# can-udp-bridge.net
KiCad netlist of a schematic drawn in EAGLE
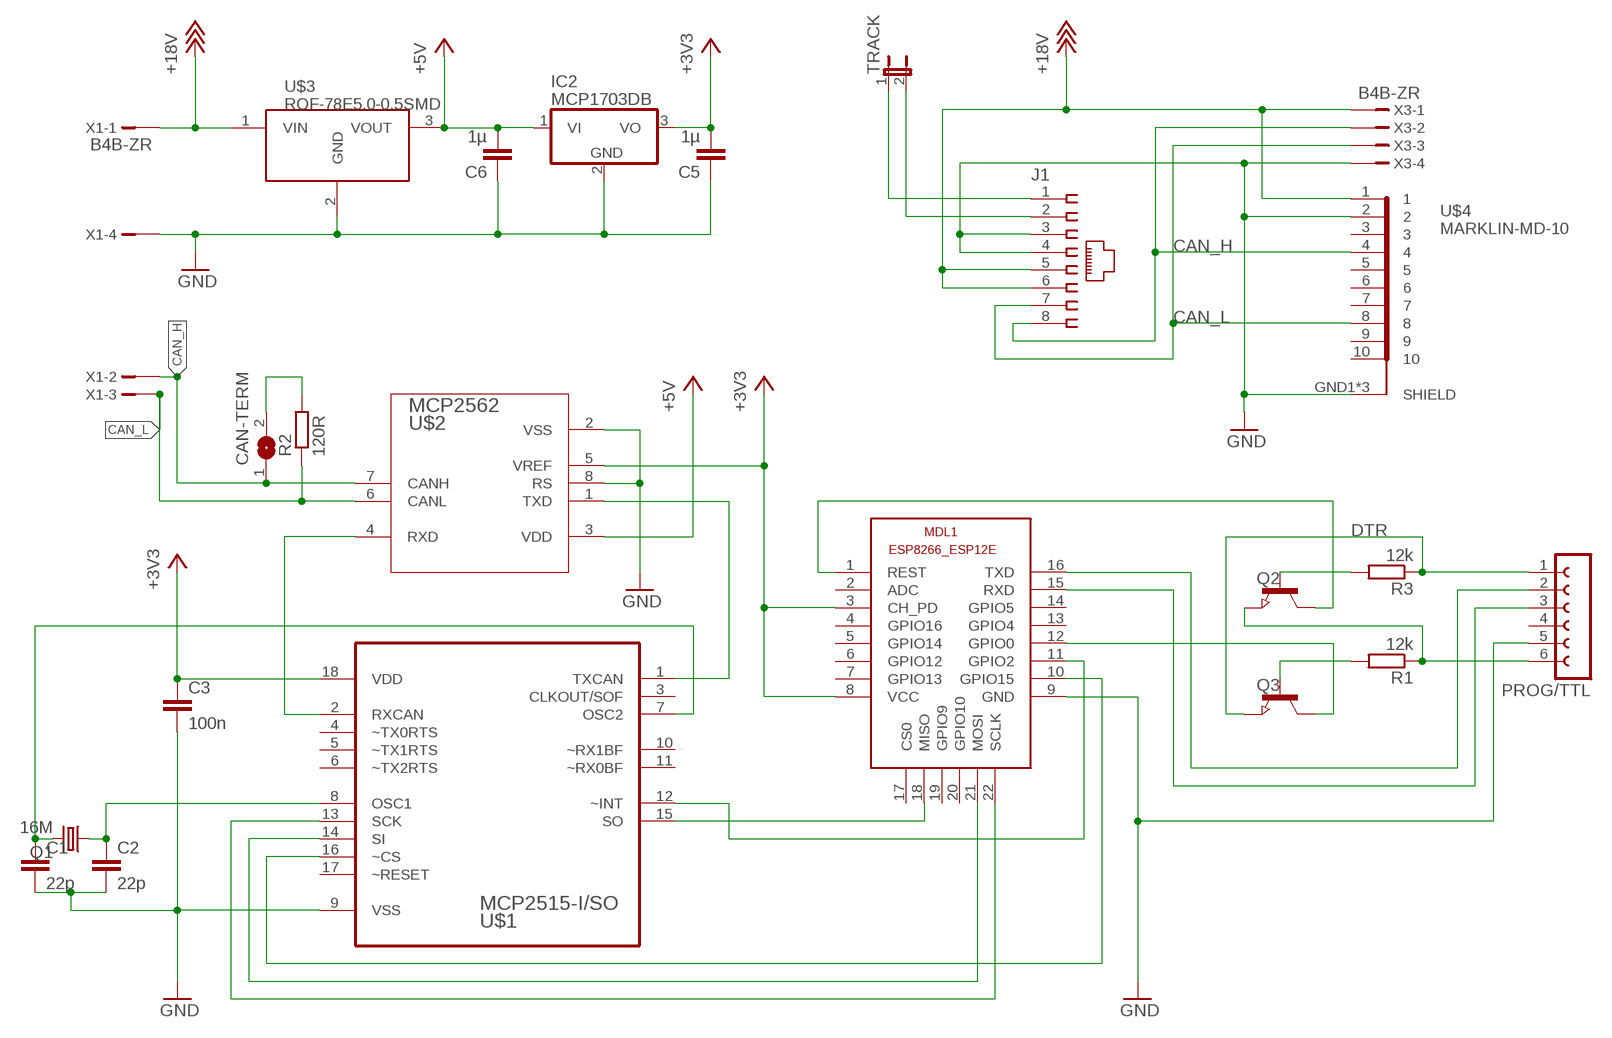
[diagram p0: schematic, sheet 1]

(export (version "E")
  (design (tool "Eeschema 10.0.6"))
  (components
    (comp (ref "C1")
      (value "22p")
      (footprint "eagle-import:C0805")
      (libsource (lib "eagle-import") (part "C-EUC0805"))
    )
    (comp (ref "C2")
      (value "22p")
      (footprint "eagle-import:C0805")
      (libsource (lib "eagle-import") (part "C-EUC0805"))
    )
    (comp (ref "C3")
      (value "100n")
      (footprint "eagle-import:C0805")
      (libsource (lib "eagle-import") (part "C-EUC0805"))
    )
    (comp (ref "C5")
      (value "1µ")
      (footprint "eagle-import:C0805")
      (libsource (lib "eagle-import") (part "C-EUC0805"))
    )
    (comp (ref "C6")
      (value "1µ")
      (footprint "eagle-import:C0805")
      (libsource (lib "eagle-import") (part "C-EUC0805"))
    )
    (comp (ref "CAN-TERM")
      (value "SJ")
      (footprint "eagle-import:SJ")
      (libsource (lib "eagle-import") (part "SJ"))
    )
    (comp (ref "IC2")
      (value "MCP1703DB")
      (footprint "eagle-import:SOT223")
      (libsource (lib "eagle-import") (part "MCP1703DB"))
    )
    (comp (ref "J1")
      (value "215877-7")
      (footprint "eagle-import:215877-7")
      (libsource (lib "eagle-import") (part "215877-7"))
    )
    (comp (ref "MDL1")
      (value "ESP8266-12EESP8266-ESP12E")
      (footprint "eagle-import:ESP8266-ESP12E")
      (libsource (lib "eagle-import") (part "ESP8266-12EESP8266-ESP12E"))
    )
    (comp (ref "PROG/TTL")
      (value "FE06W")
      (footprint "eagle-import:FE06W")
      (libsource (lib "eagle-import") (part "FE06W"))
    )
    (comp (ref "Q1")
      (value "16M")
      (footprint "eagle-import:CTS406")
      (libsource (lib "eagle-import") (part "CRYSTALCTS406"))
    )
    (comp (ref "Q2")
      (value "NPN-TRANSISTOR_SOT23")
      (footprint "eagle-import:SOT23")
      (libsource (lib "eagle-import") (part "NPN-TRANSISTOR_SOT23"))
    )
    (comp (ref "Q3")
      (value "NPN-TRANSISTOR_SOT23")
      (footprint "eagle-import:SOT23")
      (libsource (lib "eagle-import") (part "NPN-TRANSISTOR_SOT23"))
    )
    (comp (ref "R1")
      (value "12k")
      (footprint "eagle-import:R0805")
      (libsource (lib "eagle-import") (part "R-EU_R0805"))
    )
    (comp (ref "R2")
      (value "120R")
      (footprint "eagle-import:R0805")
      (libsource (lib "eagle-import") (part "R-EU_R0805"))
    )
    (comp (ref "R3")
      (value "12k")
      (footprint "eagle-import:R0805")
      (libsource (lib "eagle-import") (part "R-EU_R0805"))
    )
    (comp (ref "TRACK")
      (value "JP1E")
      (footprint "eagle-import:JP1")
      (libsource (lib "eagle-import") (part "JP1E"))
    )
    (comp (ref "U$1")
      (value "MCP2515-I/SO")
      (footprint "eagle-import:SOIC127P1034X264-18N")
      (libsource (lib "eagle-import") (part "MCP2515-I/SO"))
    )
    (comp (ref "U$2")
      (value "MCP2562")
      (footprint "eagle-import:SOIC127P600X175-8N")
      (fields (field (name "MPN") "MCP2551-E/SN"))
      (libsource (lib "eagle-import") (part "MCP2551-E/SN"))
    )
    (comp (ref "U$3")
      (value "ROF-78E5.0-0.5SMD")
      (footprint "eagle-import:ROF-78EXX-0.5SMD")
      (libsource (lib "eagle-import") (part "ROF-78E5.0-0.5SMD"))
    )
    (comp (ref "U$4")
      (value "MARKLIN-MD-10")
      (footprint "eagle-import:MARKLIN-MD-10-PRINT")
      (libsource (lib "eagle-import") (part "MARKLIN-MD-10"))
    )
    (comp (ref "X1")
      (value "B4B-ZR")
      (footprint "eagle-import:B4B-ZR")
      (fields (field (name "MF") "FARNELL") (field (name "MPN") "B4B-ZR(LF)(SN)"))
      (libsource (lib "eagle-import") (part "?4B-ZRB"))
    )
    (comp (ref "X3")
      (value "B4B-ZR")
      (footprint "eagle-import:B4B-ZR")
      (fields (field (name "MF") "FARNELL") (field (name "MPN") "B4B-ZR(LF)(SN)"))
      (libsource (lib "eagle-import") (part "?4B-ZRB"))
    )
  )
  (nets
    (net (code "1") (name "+3V3") (class "Default")
      (node (ref "C3") (pin "1") (pinfunction "1_1") (pintype "passive"))
      (node (ref "C5") (pin "2") (pinfunction "2_2") (pintype "passive"))
      (node (ref "IC2") (pin "3") (pinfunction "VO_3") (pintype "passive"))
      (node (ref "MDL1") (pin "3") (pinfunction "CH_PD_3") (pintype "bidirectional"))
      (node (ref "MDL1") (pin "8") (pinfunction "VCC_8") (pintype "bidirectional"))
      (node (ref "U$1") (pin "18") (pinfunction "VDD_18") (pintype "power_in"))
      (node (ref "U$2") (pin "5") (pinfunction "VREF_5") (pintype "input"))
    )
    (net (code "2") (name "+5V") (class "Default")
      (node (ref "C6") (pin "2") (pinfunction "2_2") (pintype "passive"))
      (node (ref "IC2") (pin "1") (pinfunction "VI_1") (pintype "input"))
      (node (ref "U$2") (pin "3") (pinfunction "VDD_3") (pintype "power_in"))
      (node (ref "U$3") (pin "3") (pinfunction "VOUT_3") (pintype "bidirectional"))
    )
    (net (code "3") (name "+18V") (class "Default")
      (node (ref "J1") (pin "5") (pinfunction "5_5") (pintype "passive"))
      (node (ref "J1") (pin "6") (pinfunction "6_6") (pintype "passive"))
      (node (ref "U$3") (pin "1") (pinfunction "VIN_1") (pintype "bidirectional"))
      (node (ref "U$4") (pin "1") (pinfunction "1_1") (pintype "bidirectional"))
      (node (ref "X1") (pin "1") (pinfunction "1_1") (pintype "passive"))
      (node (ref "X3") (pin "1") (pinfunction "1_1") (pintype "passive"))
    )
    (net (code "4") (name "/DTR") (class "Default")
      (node (ref "PROG/TTL") (pin "1") (pinfunction "1_1") (pintype "passive"))
      (node (ref "Q3") (pin "2") (pinfunction "E_2") (pintype "passive"))
      (node (ref "R3") (pin "1") (pinfunction "1_1") (pintype "passive"))
    )
    (net (code "5") (name "CAN_H") (class "Default")
      (node (ref "CAN-TERM") (pin "1") (pinfunction "1_1") (pintype "passive"))
      (node (ref "J1") (pin "8") (pinfunction "8_8") (pintype "passive"))
      (node (ref "U$2") (pin "7") (pinfunction "CANH_7") (pintype "output"))
      (node (ref "U$4") (pin "4") (pinfunction "4_4") (pintype "bidirectional"))
      (node (ref "X1") (pin "2") (pinfunction "1_2") (pintype "passive"))
      (node (ref "X3") (pin "2") (pinfunction "1_2") (pintype "passive"))
    )
    (net (code "6") (name "CAN_L") (class "Default")
      (node (ref "J1") (pin "7") (pinfunction "7_7") (pintype "passive"))
      (node (ref "R2") (pin "1") (pinfunction "1_1") (pintype "passive"))
      (node (ref "U$2") (pin "6") (pinfunction "CANL_6") (pintype "output"))
      (node (ref "U$4") (pin "8") (pinfunction "8_8") (pintype "bidirectional"))
      (node (ref "X1") (pin "3") (pinfunction "1_3") (pintype "passive"))
      (node (ref "X3") (pin "3") (pinfunction "1_3") (pintype "passive"))
    )
    (net (code "7") (name "GND") (class "Default")
      (node (ref "C1") (pin "2") (pinfunction "2_2") (pintype "passive"))
      (node (ref "C2") (pin "2") (pinfunction "2_2") (pintype "passive"))
      (node (ref "C3") (pin "2") (pinfunction "2_2") (pintype "passive"))
      (node (ref "C5") (pin "1") (pinfunction "1_1") (pintype "passive"))
      (node (ref "C6") (pin "1") (pinfunction "1_1") (pintype "passive"))
      (node (ref "IC2") (pin "2") (pinfunction "GND_2") (pintype "passive"))
      (node (ref "J1") (pin "3") (pinfunction "3_3") (pintype "passive"))
      (node (ref "J1") (pin "4") (pinfunction "4_4") (pintype "passive"))
      (node (ref "MDL1") (pin "9") (pinfunction "GND_9") (pintype "bidirectional"))
      (node (ref "PROG/TTL") (pin "5") (pinfunction "5_5") (pintype "passive"))
      (node (ref "U$1") (pin "9") (pinfunction "VSS_9") (pintype "power_in"))
      (node (ref "U$2") (pin "2") (pinfunction "VSS_2") (pintype "power_in"))
      (node (ref "U$2") (pin "8") (pinfunction "RS_8") (pintype "input"))
      (node (ref "U$3") (pin "2") (pinfunction "GND_2") (pintype "bidirectional"))
      (node (ref "U$4") (pin "2") (pinfunction "2_2") (pintype "bidirectional"))
      (node (ref "U$4") (pin "GND1") (pinfunction "SHIELD_GND1") (pintype "bidirectional"))
      (node (ref "U$4") (pin "GND2") (pinfunction "SHIELD_GND2") (pintype "bidirectional"))
      (node (ref "U$4") (pin "GND3") (pinfunction "SHIELD_GND3") (pintype "bidirectional"))
      (node (ref "X1") (pin "4") (pinfunction "1_4") (pintype "passive"))
      (node (ref "X3") (pin "4") (pinfunction "1_4") (pintype "passive"))
    )
    (net (code "8") (name "Net-(CAN-TERM-Pad2)") (class "Default")
      (node (ref "CAN-TERM") (pin "2") (pinfunction "2_2") (pintype "passive"))
      (node (ref "R2") (pin "2") (pinfunction "2_2") (pintype "passive"))
    )
    (net (code "9") (name "Net-(J1-Pad1)") (class "Default")
      (node (ref "J1") (pin "1") (pinfunction "1_1") (pintype "passive"))
      (node (ref "TRACK") (pin "1") (pinfunction "1_1") (pintype "passive"))
    )
    (net (code "10") (name "Net-(J1-Pad2)") (class "Default")
      (node (ref "J1") (pin "2") (pinfunction "2_2") (pintype "passive"))
      (node (ref "TRACK") (pin "2") (pinfunction "2_2") (pintype "passive"))
    )
    (net (code "11") (name "Net-(MDL1-GPIO0)") (class "Default")
      (node (ref "MDL1") (pin "12") (pinfunction "GPIO0_12") (pintype "bidirectional"))
      (node (ref "Q3") (pin "3") (pinfunction "C_3") (pintype "passive"))
    )
    (net (code "12") (name "Net-(MDL1-GPIO2)") (class "Default")
      (node (ref "MDL1") (pin "11") (pinfunction "GPIO2_11") (pintype "bidirectional"))
      (node (ref "U$1") (pin "12") (pinfunction "~{INT}_12") (pintype "output"))
    )
    (net (code "13") (name "Net-(MDL1-GPIO15)") (class "Default")
      (node (ref "MDL1") (pin "10") (pinfunction "GPIO15_10") (pintype "bidirectional"))
      (node (ref "U$1") (pin "16") (pinfunction "~{CS}_16") (pintype "input"))
    )
    (net (code "14") (name "Net-(MDL1-MISO)") (class "Default")
      (node (ref "MDL1") (pin "18") (pinfunction "MISO_18") (pintype "bidirectional"))
      (node (ref "U$1") (pin "15") (pinfunction "SO_15") (pintype "output"))
    )
    (net (code "15") (name "Net-(MDL1-MOSI)") (class "Default")
      (node (ref "MDL1") (pin "21") (pinfunction "MOSI_21") (pintype "bidirectional"))
      (node (ref "U$1") (pin "14") (pinfunction "SI_14") (pintype "input"))
    )
    (net (code "16") (name "Net-(MDL1-REST)") (class "Default")
      (node (ref "MDL1") (pin "1") (pinfunction "REST_1") (pintype "bidirectional"))
      (node (ref "Q2") (pin "3") (pinfunction "C_3") (pintype "passive"))
    )
    (net (code "17") (name "Net-(MDL1-RXD)") (class "Default")
      (node (ref "MDL1") (pin "15") (pinfunction "RXD_15") (pintype "bidirectional"))
      (node (ref "PROG/TTL") (pin "3") (pinfunction "3_3") (pintype "passive"))
    )
    (net (code "18") (name "Net-(MDL1-SCLK)") (class "Default")
      (node (ref "MDL1") (pin "22") (pinfunction "SCLK_22") (pintype "bidirectional"))
      (node (ref "U$1") (pin "13") (pinfunction "SCK_13") (pintype "input"))
    )
    (net (code "19") (name "Net-(MDL1-TXD)") (class "Default")
      (node (ref "MDL1") (pin "16") (pinfunction "TXD_16") (pintype "bidirectional"))
      (node (ref "PROG/TTL") (pin "2") (pinfunction "2_2") (pintype "passive"))
    )
    (net (code "20") (name "Net-(Q1-2)") (class "Default")
      (node (ref "C1") (pin "1") (pinfunction "1_1") (pintype "passive"))
      (node (ref "Q1") (pin "3") (pinfunction "2_3") (pintype "passive"))
      (node (ref "U$1") (pin "7") (pinfunction "OSC2_7") (pintype "output"))
    )
    (net (code "21") (name "Net-(Q2-B)") (class "Default")
      (node (ref "Q2") (pin "1") (pinfunction "B_1") (pintype "passive"))
      (node (ref "R3") (pin "2") (pinfunction "2_2") (pintype "passive"))
    )
    (net (code "22") (name "Net-(Q2-E)") (class "Default")
      (node (ref "PROG/TTL") (pin "6") (pinfunction "6_6") (pintype "passive"))
      (node (ref "Q2") (pin "2") (pinfunction "E_2") (pintype "passive"))
      (node (ref "R1") (pin "1") (pinfunction "1_1") (pintype "passive"))
    )
    (net (code "23") (name "Net-(Q3-B)") (class "Default")
      (node (ref "Q3") (pin "1") (pinfunction "B_1") (pintype "passive"))
      (node (ref "R1") (pin "2") (pinfunction "2_2") (pintype "passive"))
    )
    (net (code "24") (name "Net-(U$1-OSC1)") (class "Default")
      (node (ref "C2") (pin "1") (pinfunction "1_1") (pintype "passive"))
      (node (ref "Q1") (pin "1") (pinfunction "1_1") (pintype "passive"))
      (node (ref "U$1") (pin "8") (pinfunction "OSC1_8") (pintype "input"))
    )
    (net (code "25") (name "Net-(U$1-RXCAN)") (class "Default")
      (node (ref "U$1") (pin "2") (pinfunction "RXCAN_2") (pintype "input"))
      (node (ref "U$2") (pin "4") (pinfunction "RXD_4") (pintype "output"))
    )
    (net (code "26") (name "Net-(U$1-TXCAN)") (class "Default")
      (node (ref "U$1") (pin "1") (pinfunction "TXCAN_1") (pintype "output"))
      (node (ref "U$2") (pin "1") (pinfunction "TXD_1") (pintype "input"))
    )
    (net (code "27") (name "unconnected-(MDL1-ADC-Pad2)") (class "Default")
      (node (ref "MDL1") (pin "2") (pinfunction "ADC_2") (pintype "bidirectional"))
    )
    (net (code "28") (name "unconnected-(MDL1-CS0-Pad17)") (class "Default")
      (node (ref "MDL1") (pin "17") (pinfunction "CS0_17") (pintype "bidirectional"))
    )
    (net (code "29") (name "unconnected-(MDL1-GPIO4-Pad13)") (class "Default")
      (node (ref "MDL1") (pin "13") (pinfunction "GPIO4_13") (pintype "bidirectional"))
    )
    (net (code "30") (name "unconnected-(MDL1-GPIO5-Pad14)") (class "Default")
      (node (ref "MDL1") (pin "14") (pinfunction "GPIO5_14") (pintype "bidirectional"))
    )
    (net (code "31") (name "unconnected-(MDL1-GPIO9-Pad19)") (class "Default")
      (node (ref "MDL1") (pin "19") (pinfunction "GPIO9_19") (pintype "bidirectional"))
    )
    (net (code "32") (name "unconnected-(MDL1-GPIO10-Pad20)") (class "Default")
      (node (ref "MDL1") (pin "20") (pinfunction "GPIO10_20") (pintype "bidirectional"))
    )
    (net (code "33") (name "unconnected-(MDL1-GPIO12-Pad6)") (class "Default")
      (node (ref "MDL1") (pin "6") (pinfunction "GPIO12_6") (pintype "bidirectional"))
    )
    (net (code "34") (name "unconnected-(MDL1-GPIO13-Pad7)") (class "Default")
      (node (ref "MDL1") (pin "7") (pinfunction "GPIO13_7") (pintype "bidirectional"))
    )
    (net (code "35") (name "unconnected-(MDL1-GPIO14-Pad5)") (class "Default")
      (node (ref "MDL1") (pin "5") (pinfunction "GPIO14_5") (pintype "bidirectional"))
    )
    (net (code "36") (name "unconnected-(MDL1-GPIO16-Pad4)") (class "Default")
      (node (ref "MDL1") (pin "4") (pinfunction "GPIO16_4") (pintype "bidirectional"))
    )
    (net (code "37") (name "unconnected-(PROG/TTL-Pad4)") (class "Default")
      (node (ref "PROG/TTL") (pin "4") (pinfunction "4_4") (pintype "passive"))
    )
    (net (code "38") (name "unconnected-(U$1-CLKOUT{slash}SOF-Pad3)") (class "Default")
      (node (ref "U$1") (pin "3") (pinfunction "CLKOUT/SOF_3") (pintype "output"))
    )
    (net (code "39") (name "unconnected-(U$1-~{RESET}-Pad17)") (class "Default")
      (node (ref "U$1") (pin "17") (pinfunction "~{RESET}_17") (pintype "input"))
    )
    (net (code "40") (name "unconnected-(U$1-~{RX0BF}-Pad11)") (class "Default")
      (node (ref "U$1") (pin "11") (pinfunction "~{RX0BF}_11") (pintype "output"))
    )
    (net (code "41") (name "unconnected-(U$1-~{RX1BF}-Pad10)") (class "Default")
      (node (ref "U$1") (pin "10") (pinfunction "~{RX1BF}_10") (pintype "output"))
    )
    (net (code "42") (name "unconnected-(U$1-~{TX0RTS}-Pad4)") (class "Default")
      (node (ref "U$1") (pin "4") (pinfunction "~{TX0RTS}_4") (pintype "input"))
    )
    (net (code "43") (name "unconnected-(U$1-~{TX1RTS}-Pad5)") (class "Default")
      (node (ref "U$1") (pin "5") (pinfunction "~{TX1RTS}_5") (pintype "input"))
    )
    (net (code "44") (name "unconnected-(U$1-~{TX2RTS}-Pad6)") (class "Default")
      (node (ref "U$1") (pin "6") (pinfunction "~{TX2RTS}_6") (pintype "input"))
    )
    (net (code "45") (name "unconnected-(U$4-Pad3)") (class "Default")
      (node (ref "U$4") (pin "3") (pinfunction "3_3") (pintype "bidirectional"))
    )
    (net (code "46") (name "unconnected-(U$4-Pad5)") (class "Default")
      (node (ref "U$4") (pin "5") (pinfunction "5_5") (pintype "bidirectional"))
    )
    (net (code "47") (name "unconnected-(U$4-Pad6)") (class "Default")
      (node (ref "U$4") (pin "6") (pinfunction "6_6") (pintype "bidirectional"))
    )
    (net (code "48") (name "unconnected-(U$4-Pad7)") (class "Default")
      (node (ref "U$4") (pin "7") (pinfunction "7_7") (pintype "bidirectional"))
    )
    (net (code "49") (name "unconnected-(U$4-Pad9)") (class "Default")
      (node (ref "U$4") (pin "9") (pinfunction "9_9") (pintype "bidirectional"))
    )
    (net (code "50") (name "unconnected-(U$4-Pad10)") (class "Default")
      (node (ref "U$4") (pin "10") (pinfunction "10_10") (pintype "bidirectional"))
    )
  )
)
